# 1-Schematic_ACSE.net
KiCad netlist of a schematic drawn in EasyEDA
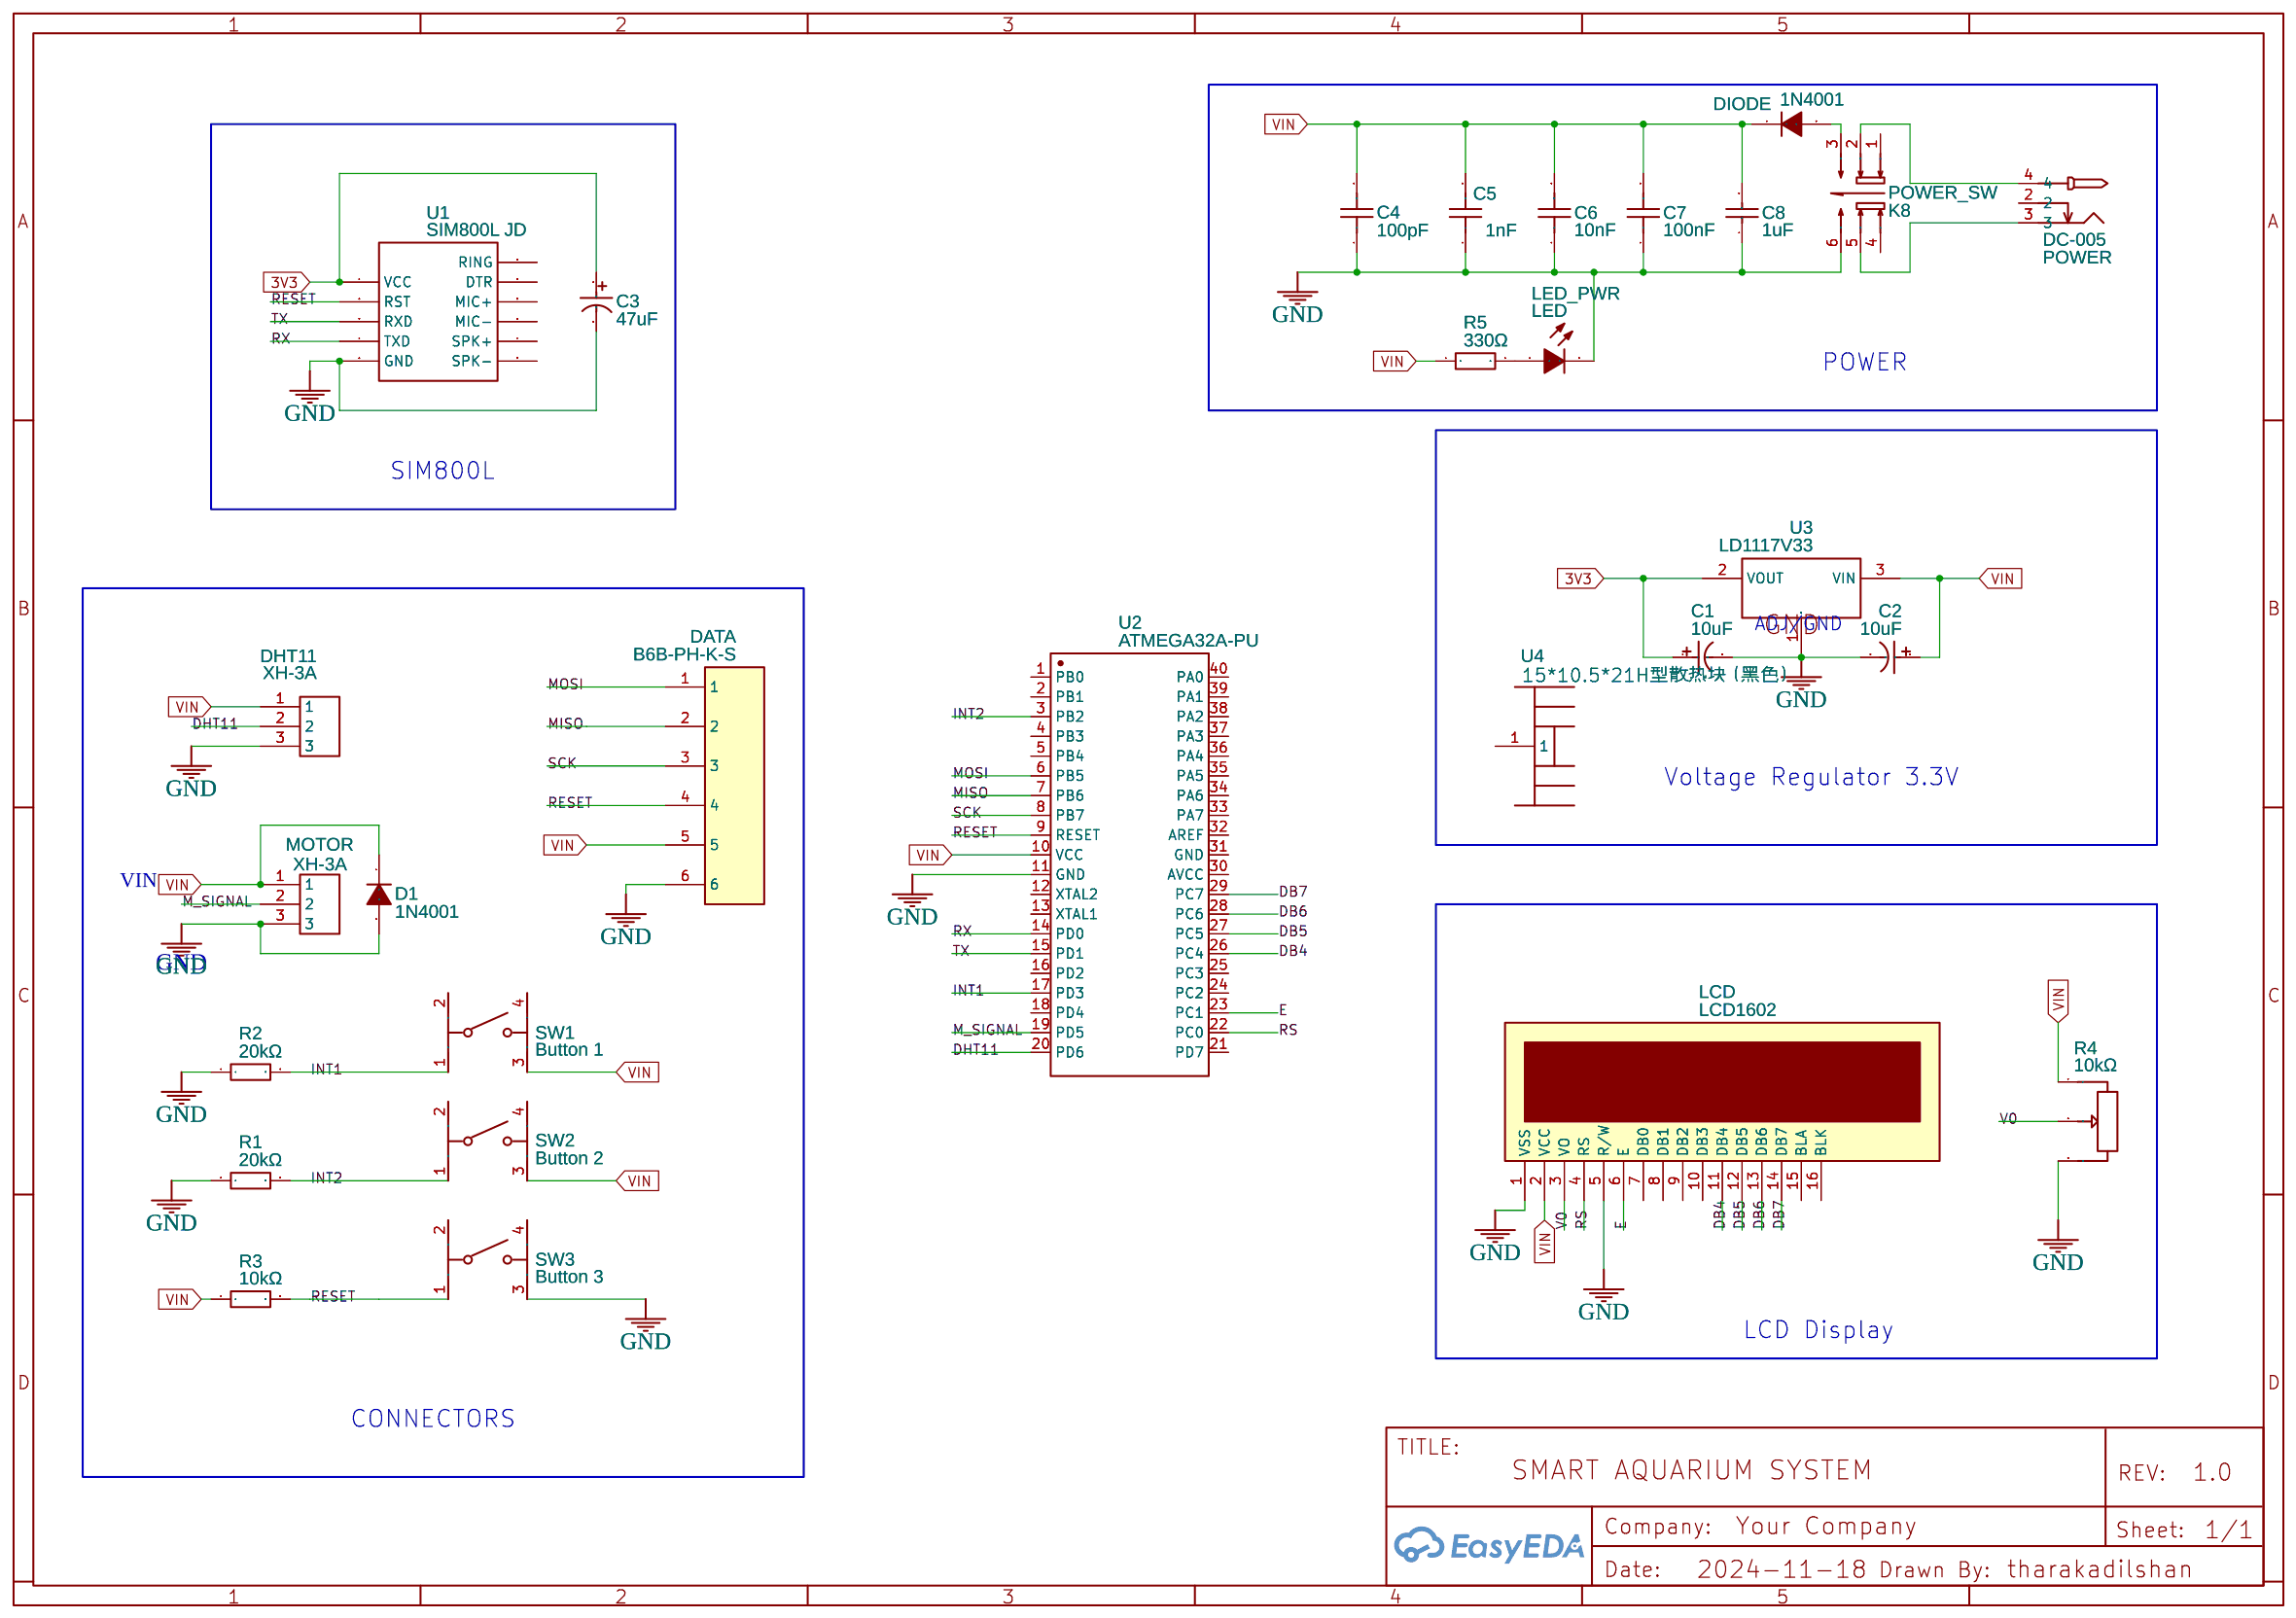
[diagram p0: schematic sheet]

(export (version "E")
  (design (tool "Eeschema 10.0.6"))
  (components
    (comp (ref "C1")
      (value "10uF")
      (fields
        (field (name "Manufacturer Part") "KM106M100E11RR0VH2FP0")
        (field (name "Manufacturer") "CX(承兴)")
      )
      (libsource (lib "") (part "10uf/100V"))
    )
    (comp (ref "C2")
      (value "10uF")
      (fields
        (field (name "Manufacturer Part") "KM106M100E11RR0VH2FP0")
        (field (name "Manufacturer") "CX(承兴)")
      )
      (libsource (lib "") (part "10uf/100V_1"))
    )
    (comp (ref "C3")
      (value "47uF")
      (fields
        (field (name "Manufacturer Part") "KS476M016D07RR0VH2FP0")
        (field (name "Manufacturer") "CX(承兴)")
      )
      (libsource (lib "") (part "47UF16V"))
    )
    (comp (ref "C4")
      (value "100pF")
      (fields
        (field (name "Manufacturer Part") "CC1H101KC4PDSL4B30MF")
        (field (name "Manufacturer") "Dersonic(德尔创)")
      )
      (libsource (lib "") (part "CC1H101KC4PDSL4B30MF"))
    )
    (comp (ref "C5")
      (value "1nF")
      (fields
        (field (name "Manufacturer Part") "CC1H102MC1PDB44B30MF")
        (field (name "Manufacturer") "Dersonic(德尔创)")
      )
      (libsource (lib "") (part "CC1H102MC1PDB44B30MF"))
    )
    (comp (ref "C6")
      (value "10nF")
      (fields
        (field (name "Manufacturer Part") "CC1H103ZC4PD3F4D30MF")
        (field (name "Manufacturer") "Dersonic(德尔创)")
      )
      (libsource (lib "") (part "CC1H103ZC4PD3F4D30MF"))
    )
    (comp (ref "C7")
      (value "100nF")
      (fields
        (field (name "Manufacturer Part") "CC1H104ZC1PD3F5P30MF")
        (field (name "Manufacturer") "Dersonic(德尔创)")
      )
      (libsource (lib "") (part "CC1H104ZC1PD3F5P30MF"))
    )
    (comp (ref "C8")
      (value "1uF")
      (fields (field (name "Manufacturer Part") "SR305C105KAR") (field (name "Manufacturer") "Kyocera AVX"))
      (libsource (lib "") (part "SR305C105KAR"))
    )
    (comp (ref "D1")
      (value "1N4001")
      (fields (field (name "Manufacturer Part") "1N4001-E3/73") (field (name "Manufacturer") "VISHAY(威世)"))
      (libsource (lib "") (part "1N4001-E3/73"))
    )
    (comp (ref "DATA")
      (value "B6B-PH-K-S")
      (fields (field (name "Manufacturer Part") "B6B-PH-K-S(LF)(SN)") (field (name "Manufacturer") "JST"))
      (libsource (lib "") (part "B6B-PH-K-S(LF)(SN)"))
    )
    (comp (ref "DHT11")
      (value "XH-3A")
      (fields (field (name "Manufacturer") "BOOMELE(博穆精密)"))
      (libsource (lib "") (part "XH-3A_1"))
    )
    (comp (ref "DIODE")
      (value "1N4001")
      (fields (field (name "Manufacturer Part") "1N4001-E3/73") (field (name "Manufacturer") "VISHAY(威世)"))
      (libsource (lib "") (part "1N4001-E3/73_1"))
    )
    (comp (ref "LCD")
      (value "LCD1602")
      (fields
        (field (name "Manufacturer Part") "LCM1602K-NSW-BBW")
        (field (name "Manufacturer") "LONTECH(厦门龙特)")
      )
      (libsource (lib "") (part "LCD1602"))
    )
    (comp (ref "LED_PWR")
      (value "LED")
      (fields
        (field (name "Manufacturer Part") "204-10SDRD/S530-A3-L")
        (field (name "Manufacturer") "EVERLIGHT(亿光)")
      )
      (libsource (lib "") (part "204-10SDRD/S530-A3-L"))
    )
    (comp (ref "MOTOR")
      (value "XH-3A")
      (fields (field (name "Manufacturer") "BOOMELE(博穆精密)"))
      (libsource (lib "") (part "XH-3A"))
    )
    (comp (ref "POWER")
      (value "DC-005")
      (fields (field (name "Manufacturer Part") "DC-005 2.0") (field (name "Manufacturer") "BOOMELE(博穆精密)"))
      (libsource (lib "") (part "DC-005 5.5-2.0MM"))
    )
    (comp (ref "POWER_SW")
      (value "K8")
      (fields (field (name "Manufacturer Part") "K8-7071D-L1") (field (name "Manufacturer") "韩国韩荣"))
      (libsource (lib "") (part "K8-7071D-L1"))
    )
    (comp (ref "R1")
      (value "20kΩ")
      (fields
        (field (name "Manufacturer Part") "MFR0W4F2002A50")
        (field (name "Manufacturer") "UNI-ROYAL(厚声)")
      )
      (libsource (lib "") (part "MFR0W4F2002A50"))
    )
    (comp (ref "R2")
      (value "20kΩ")
      (fields
        (field (name "Manufacturer Part") "MFR0W4F2002A50")
        (field (name "Manufacturer") "UNI-ROYAL(厚声)")
      )
      (libsource (lib "") (part "MFR0W4F2002A50"))
    )
    (comp (ref "R3")
      (value "10kΩ")
      (fields
        (field (name "Manufacturer Part") "CFR0W4J0103A50")
        (field (name "Manufacturer") "UNI-ROYAL(厚声)")
      )
      (libsource (lib "") (part "CFR0W4J0103A50"))
    )
    (comp (ref "R4")
      (value "10kΩ")
      (fields
        (field (name "Manufacturer Part") "CT-6ETV 10K OHM (103)")
        (field (name "Manufacturer") "NIDEC(尼得科)")
      )
      (libsource (lib "") (part "CT-6ETV 10K OHM (103)"))
    )
    (comp (ref "R5")
      (value "330Ω")
      (fields
        (field (name "Manufacturer Part") "CFR0W4J0331A50")
        (field (name "Manufacturer") "UNI-ROYAL(厚声)")
      )
      (libsource (lib "") (part "CFR0W4J0331A50"))
    )
    (comp (ref "SW1")
      (value "Button 1")
      (fields (field (name "Manufacturer Part") "C268224") (field (name "Manufacturer") "BBJ"))
      (libsource (lib "") (part "Button-6x6x6mm"))
    )
    (comp (ref "SW2")
      (value "Button 2")
      (fields
        (field (name "Manufacturer Part") "Switch,6*6*6Plastic head,260G, 0.25mm,Straight line")
        (field (name "Manufacturer") "BBJ")
      )
      (libsource (lib "") (part "Button-6x6x6mm"))
    )
    (comp (ref "SW3")
      (value "Button 3")
      (fields
        (field (name "Manufacturer Part") "Switch,6*6*6Plastic head,260G, 0.25mm,Straight line")
        (field (name "Manufacturer") "BBJ")
      )
      (libsource (lib "") (part "Button-6x6x6mm"))
    )
    (comp (ref "U1") (value "SIM800L JD") (libsource (lib "") (part "SIM800L JD")))
    (comp (ref "U2")
      (value "ATMEGA32A-PU")
      (fields (field (name "Manufacturer") "MICROCHIP(美国微芯)"))
      (libsource (lib "") (part "ATMEGA32A-PU"))
    )
    (comp (ref "U3")
      (value "LD1117V33")
      (fields (field (name "Manufacturer") "ST(意法半导体)"))
      (libsource (lib "") (part "LD1117V33"))
    )
    (comp (ref "U4")
      (value "15*10.5*21H型散热块（黑色）")
      (fields (field (name "Manufacturer Part") "15*10.5*21") (field (name "Manufacturer") "XSD(鑫顺达)"))
      (libsource (lib "") (part "15*10.5*21H型散热块（黑色）"))
    )
  )
  (nets
    (net (code "1") (name "/DB4") (class "Default")
      (node (ref "LCD") (pin "11") (pinfunction "DB4_11") (pintype "unspecified"))
      (node (ref "U2") (pin "26") (pinfunction "PC4_26") (pintype "unspecified"))
    )
    (net (code "2") (name "/DB5") (class "Default")
      (node (ref "LCD") (pin "12") (pinfunction "DB5_12") (pintype "unspecified"))
      (node (ref "U2") (pin "27") (pinfunction "PC5_27") (pintype "unspecified"))
    )
    (net (code "3") (name "/DB6") (class "Default")
      (node (ref "LCD") (pin "13") (pinfunction "DB6_13") (pintype "unspecified"))
      (node (ref "U2") (pin "28") (pinfunction "PC6_28") (pintype "unspecified"))
    )
    (net (code "4") (name "/DB7") (class "Default")
      (node (ref "LCD") (pin "14") (pinfunction "DB7_14") (pintype "unspecified"))
      (node (ref "U2") (pin "29") (pinfunction "PC7_29") (pintype "unspecified"))
    )
    (net (code "5") (name "/DHT11") (class "Default")
      (node (ref "DHT11") (pin "2") (pinfunction "2_2") (pintype "unspecified"))
      (node (ref "U2") (pin "20") (pinfunction "PD6_20") (pintype "unspecified"))
    )
    (net (code "6") (name "/E") (class "Default")
      (node (ref "LCD") (pin "6") (pinfunction "E_6") (pintype "unspecified"))
      (node (ref "U2") (pin "23") (pinfunction "PC1_23") (pintype "unspecified"))
    )
    (net (code "7") (name "/INT1") (class "Default")
      (node (ref "R2") (pin "2") (pinfunction "2_2") (pintype "input"))
      (node (ref "SW1") (pin "1") (pinfunction "1_1") (pintype "unspecified"))
      (node (ref "U2") (pin "17") (pinfunction "PD3_17") (pintype "unspecified"))
    )
    (net (code "8") (name "/INT2") (class "Default")
      (node (ref "R1") (pin "2") (pinfunction "2_2") (pintype "input"))
      (node (ref "SW2") (pin "1") (pinfunction "1_1") (pintype "unspecified"))
      (node (ref "U2") (pin "3") (pinfunction "PB2_3") (pintype "unspecified"))
    )
    (net (code "9") (name "/MISO") (class "Default")
      (node (ref "DATA") (pin "2") (pinfunction "2_2") (pintype "input"))
      (node (ref "U2") (pin "7") (pinfunction "PB6_7") (pintype "unspecified"))
    )
    (net (code "10") (name "/MOSI") (class "Default")
      (node (ref "DATA") (pin "1") (pinfunction "1_1") (pintype "input"))
      (node (ref "U2") (pin "6") (pinfunction "PB5_6") (pintype "unspecified"))
    )
    (net (code "11") (name "/M_SIGNAL") (class "Default")
      (node (ref "MOTOR") (pin "2") (pinfunction "2_2") (pintype "unspecified"))
      (node (ref "U2") (pin "19") (pinfunction "PD5_19") (pintype "unspecified"))
    )
    (net (code "12") (name "/RESET") (class "Default")
      (node (ref "DATA") (pin "4") (pinfunction "4_4") (pintype "input"))
      (node (ref "R3") (pin "2") (pinfunction "2_2") (pintype "input"))
      (node (ref "SW3") (pin "1") (pinfunction "1_1") (pintype "unspecified"))
      (node (ref "U1") (pin "2") (pinfunction "RST_2") (pintype "unspecified"))
      (node (ref "U2") (pin "9") (pinfunction "RESET_9") (pintype "unspecified"))
    )
    (net (code "13") (name "/RS") (class "Default")
      (node (ref "LCD") (pin "4") (pinfunction "RS_4") (pintype "unspecified"))
      (node (ref "U2") (pin "22") (pinfunction "PC0_22") (pintype "unspecified"))
    )
    (net (code "14") (name "/RX") (class "Default")
      (node (ref "U1") (pin "4") (pinfunction "TXD_4") (pintype "unspecified"))
      (node (ref "U2") (pin "14") (pinfunction "PD0_14") (pintype "unspecified"))
    )
    (net (code "15") (name "/SCK") (class "Default")
      (node (ref "DATA") (pin "3") (pinfunction "3_3") (pintype "input"))
      (node (ref "U2") (pin "8") (pinfunction "PB7_8") (pintype "unspecified"))
    )
    (net (code "16") (name "/TX") (class "Default")
      (node (ref "U1") (pin "3") (pinfunction "RXD_3") (pintype "unspecified"))
      (node (ref "U2") (pin "15") (pinfunction "PD1_15") (pintype "unspecified"))
    )
    (net (code "17") (name "/V0") (class "Default")
      (node (ref "LCD") (pin "3") (pinfunction "VO_3") (pintype "unspecified"))
      (node (ref "R4") (pin "2") (pinfunction "2_2") (pintype "unspecified"))
    )
    (net (code "18") (name "3V3") (class "Default")
      (node (ref "C1") (pin "1") (pinfunction "1_1") (pintype "input"))
      (node (ref "C3") (pin "1") (pinfunction "1_1") (pintype "input"))
      (node (ref "U1") (pin "1") (pinfunction "VCC_1") (pintype "unspecified"))
      (node (ref "U3") (pin "2") (pinfunction "VOUT_2") (pintype "passive"))
    )
    (net (code "19") (name "GND") (class "Default")
      (node (ref "C1") (pin "2") (pinfunction "2_2") (pintype "input"))
      (node (ref "C2") (pin "2") (pinfunction "2_2") (pintype "input"))
      (node (ref "C3") (pin "2") (pinfunction "2_2") (pintype "input"))
      (node (ref "C4") (pin "1") (pinfunction "1_1") (pintype "unspecified"))
      (node (ref "C5") (pin "1") (pinfunction "1_1") (pintype "unspecified"))
      (node (ref "C6") (pin "1") (pinfunction "1_1") (pintype "unspecified"))
      (node (ref "C7") (pin "1") (pinfunction "1_1") (pintype "unspecified"))
      (node (ref "C8") (pin "1") (pinfunction "1_1") (pintype "input"))
      (node (ref "D1") (pin "2") (pinfunction "A_2") (pintype "unspecified"))
      (node (ref "DATA") (pin "6") (pinfunction "6_6") (pintype "input"))
      (node (ref "DHT11") (pin "3") (pinfunction "3_3") (pintype "unspecified"))
      (node (ref "LCD") (pin "1") (pinfunction "VSS_1") (pintype "unspecified"))
      (node (ref "LCD") (pin "5") (pinfunction "R/W_5") (pintype "unspecified"))
      (node (ref "LED_PWR") (pin "2") (pinfunction "C_2") (pintype "input"))
      (node (ref "MOTOR") (pin "3") (pinfunction "3_3") (pintype "unspecified"))
      (node (ref "POWER_SW") (pin "6") (pinfunction "6_6") (pintype "unspecified"))
      (node (ref "R1") (pin "1") (pinfunction "1_1") (pintype "input"))
      (node (ref "R2") (pin "1") (pinfunction "1_1") (pintype "input"))
      (node (ref "R4") (pin "3") (pinfunction "3_3") (pintype "unspecified"))
      (node (ref "SW3") (pin "3") (pinfunction "3_3") (pintype "unspecified"))
      (node (ref "U1") (pin "5") (pinfunction "GND_5") (pintype "unspecified"))
      (node (ref "U2") (pin "11") (pinfunction "GND_11") (pintype "unspecified"))
      (node (ref "U3") (pin "1") (pinfunction "GND_1") (pintype "unspecified"))
    )
    (net (code "20") (name "Net-(DIODE-A)") (class "Default")
      (node (ref "DIODE") (pin "2") (pinfunction "A_2") (pintype "unspecified"))
      (node (ref "POWER_SW") (pin "3") (pinfunction "3_3") (pintype "unspecified"))
    )
    (net (code "21") (name "Net-(LED_PWR-A)") (class "Default")
      (node (ref "LED_PWR") (pin "1") (pinfunction "A_1") (pintype "input"))
      (node (ref "R5") (pin "2") (pinfunction "2_2") (pintype "input"))
    )
    (net (code "22") (name "Net-(POWER-Pad3)") (class "Default")
      (node (ref "POWER") (pin "3") (pinfunction "3_3") (pintype "unspecified"))
      (node (ref "POWER_SW") (pin "5") (pinfunction "5_5") (pintype "unspecified"))
    )
    (net (code "23") (name "Net-(POWER-Pad4)") (class "Default")
      (node (ref "POWER") (pin "4") (pinfunction "4_4") (pintype "unspecified"))
      (node (ref "POWER_SW") (pin "2") (pinfunction "2_2") (pintype "unspecified"))
    )
    (net (code "24") (name "VIN") (class "Default")
      (node (ref "C2") (pin "1") (pinfunction "1_1") (pintype "input"))
      (node (ref "C4") (pin "2") (pinfunction "2_2") (pintype "unspecified"))
      (node (ref "C5") (pin "2") (pinfunction "2_2") (pintype "unspecified"))
      (node (ref "C6") (pin "2") (pinfunction "2_2") (pintype "unspecified"))
      (node (ref "C7") (pin "2") (pinfunction "2_2") (pintype "unspecified"))
      (node (ref "C8") (pin "2") (pinfunction "2_2") (pintype "input"))
      (node (ref "D1") (pin "1") (pinfunction "K_1") (pintype "unspecified"))
      (node (ref "DATA") (pin "5") (pinfunction "5_5") (pintype "input"))
      (node (ref "DHT11") (pin "1") (pinfunction "1_1") (pintype "unspecified"))
      (node (ref "DIODE") (pin "1") (pinfunction "K_1") (pintype "unspecified"))
      (node (ref "LCD") (pin "2") (pinfunction "VCC_2") (pintype "unspecified"))
      (node (ref "MOTOR") (pin "1") (pinfunction "1_1") (pintype "unspecified"))
      (node (ref "R3") (pin "1") (pinfunction "1_1") (pintype "input"))
      (node (ref "R4") (pin "1") (pinfunction "1_1") (pintype "unspecified"))
      (node (ref "R5") (pin "1") (pinfunction "1_1") (pintype "input"))
      (node (ref "SW1") (pin "3") (pinfunction "3_3") (pintype "unspecified"))
      (node (ref "SW2") (pin "3") (pinfunction "3_3") (pintype "unspecified"))
      (node (ref "U2") (pin "10") (pinfunction "VCC_10") (pintype "unspecified"))
      (node (ref "U3") (pin "3") (pinfunction "VIN_3") (pintype "passive"))
    )
    (net (code "25") (name "unconnected-(LCD-BLA-Pad15)") (class "Default")
      (node (ref "LCD") (pin "15") (pinfunction "BLA_15") (pintype "unspecified"))
    )
    (net (code "26") (name "unconnected-(LCD-BLK-Pad16)") (class "Default")
      (node (ref "LCD") (pin "16") (pinfunction "BLK_16") (pintype "unspecified"))
    )
    (net (code "27") (name "unconnected-(LCD-DB0-Pad7)") (class "Default")
      (node (ref "LCD") (pin "7") (pinfunction "DB0_7") (pintype "unspecified"))
    )
    (net (code "28") (name "unconnected-(LCD-DB1-Pad8)") (class "Default")
      (node (ref "LCD") (pin "8") (pinfunction "DB1_8") (pintype "unspecified"))
    )
    (net (code "29") (name "unconnected-(LCD-DB2-Pad9)") (class "Default")
      (node (ref "LCD") (pin "9") (pinfunction "DB2_9") (pintype "unspecified"))
    )
    (net (code "30") (name "unconnected-(LCD-DB3-Pad10)") (class "Default")
      (node (ref "LCD") (pin "10") (pinfunction "DB3_10") (pintype "unspecified"))
    )
    (net (code "31") (name "unconnected-(POWER-Pad2)") (class "Default")
      (node (ref "POWER") (pin "2") (pinfunction "2_2") (pintype "unspecified"))
    )
    (net (code "32") (name "unconnected-(POWER_SW-Pad1)") (class "Default")
      (node (ref "POWER_SW") (pin "1") (pinfunction "1_1") (pintype "unspecified"))
    )
    (net (code "33") (name "unconnected-(POWER_SW-Pad4)") (class "Default")
      (node (ref "POWER_SW") (pin "4") (pinfunction "4_4") (pintype "unspecified"))
    )
    (net (code "34") (name "unconnected-(SW1-Pad2)") (class "Default")
      (node (ref "SW1") (pin "2") (pinfunction "2_2") (pintype "unspecified"))
    )
    (net (code "35") (name "unconnected-(SW1-Pad4)") (class "Default")
      (node (ref "SW1") (pin "4") (pinfunction "4_4") (pintype "unspecified"))
    )
    (net (code "36") (name "unconnected-(SW2-Pad2)") (class "Default")
      (node (ref "SW2") (pin "2") (pinfunction "2_2") (pintype "unspecified"))
    )
    (net (code "37") (name "unconnected-(SW2-Pad4)") (class "Default")
      (node (ref "SW2") (pin "4") (pinfunction "4_4") (pintype "unspecified"))
    )
    (net (code "38") (name "unconnected-(SW3-Pad2)") (class "Default")
      (node (ref "SW3") (pin "2") (pinfunction "2_2") (pintype "unspecified"))
    )
    (net (code "39") (name "unconnected-(SW3-Pad4)") (class "Default")
      (node (ref "SW3") (pin "4") (pinfunction "4_4") (pintype "unspecified"))
    )
    (net (code "40") (name "unconnected-(U1-DTR-Pad10)") (class "Default")
      (node (ref "U1") (pin "10") (pinfunction "DTR_10") (pintype "unspecified"))
    )
    (net (code "41") (name "unconnected-(U1-MIC+-Pad9)") (class "Default")
      (node (ref "U1") (pin "9") (pinfunction "MIC+_9") (pintype "unspecified"))
    )
    (net (code "42") (name "unconnected-(U1-MIC--Pad8)") (class "Default")
      (node (ref "U1") (pin "8") (pinfunction "MIC-_8") (pintype "unspecified"))
    )
    (net (code "43") (name "unconnected-(U1-RING-Pad11)") (class "Default")
      (node (ref "U1") (pin "11") (pinfunction "RING_11") (pintype "unspecified"))
    )
    (net (code "44") (name "unconnected-(U1-SPK+-Pad7)") (class "Default")
      (node (ref "U1") (pin "7") (pinfunction "SPK+_7") (pintype "unspecified"))
    )
    (net (code "45") (name "unconnected-(U1-SPK--Pad6)") (class "Default")
      (node (ref "U1") (pin "6") (pinfunction "SPK-_6") (pintype "unspecified"))
    )
    (net (code "46") (name "unconnected-(U2-AREF-Pad32)") (class "Default")
      (node (ref "U2") (pin "32") (pinfunction "AREF_32") (pintype "unspecified"))
    )
    (net (code "47") (name "unconnected-(U2-AVCC-Pad30)") (class "Default")
      (node (ref "U2") (pin "30") (pinfunction "AVCC_30") (pintype "unspecified"))
    )
    (net (code "48") (name "unconnected-(U2-GND-Pad31)") (class "Default")
      (node (ref "U2") (pin "31") (pinfunction "GND_31") (pintype "unspecified"))
    )
    (net (code "49") (name "unconnected-(U2-PA0-Pad40)") (class "Default")
      (node (ref "U2") (pin "40") (pinfunction "PA0_40") (pintype "unspecified"))
    )
    (net (code "50") (name "unconnected-(U2-PA1-Pad39)") (class "Default")
      (node (ref "U2") (pin "39") (pinfunction "PA1_39") (pintype "unspecified"))
    )
    (net (code "51") (name "unconnected-(U2-PA2-Pad38)") (class "Default")
      (node (ref "U2") (pin "38") (pinfunction "PA2_38") (pintype "unspecified"))
    )
    (net (code "52") (name "unconnected-(U2-PA3-Pad37)") (class "Default")
      (node (ref "U2") (pin "37") (pinfunction "PA3_37") (pintype "unspecified"))
    )
    (net (code "53") (name "unconnected-(U2-PA4-Pad36)") (class "Default")
      (node (ref "U2") (pin "36") (pinfunction "PA4_36") (pintype "unspecified"))
    )
    (net (code "54") (name "unconnected-(U2-PA5-Pad35)") (class "Default")
      (node (ref "U2") (pin "35") (pinfunction "PA5_35") (pintype "unspecified"))
    )
    (net (code "55") (name "unconnected-(U2-PA6-Pad34)") (class "Default")
      (node (ref "U2") (pin "34") (pinfunction "PA6_34") (pintype "unspecified"))
    )
    (net (code "56") (name "unconnected-(U2-PA7-Pad33)") (class "Default")
      (node (ref "U2") (pin "33") (pinfunction "PA7_33") (pintype "unspecified"))
    )
    (net (code "57") (name "unconnected-(U2-PB0-Pad1)") (class "Default")
      (node (ref "U2") (pin "1") (pinfunction "PB0_1") (pintype "unspecified"))
    )
    (net (code "58") (name "unconnected-(U2-PB1-Pad2)") (class "Default")
      (node (ref "U2") (pin "2") (pinfunction "PB1_2") (pintype "unspecified"))
    )
    (net (code "59") (name "unconnected-(U2-PB3-Pad4)") (class "Default")
      (node (ref "U2") (pin "4") (pinfunction "PB3_4") (pintype "unspecified"))
    )
    (net (code "60") (name "unconnected-(U2-PB4-Pad5)") (class "Default")
      (node (ref "U2") (pin "5") (pinfunction "PB4_5") (pintype "unspecified"))
    )
    (net (code "61") (name "unconnected-(U2-PC2-Pad24)") (class "Default")
      (node (ref "U2") (pin "24") (pinfunction "PC2_24") (pintype "unspecified"))
    )
    (net (code "62") (name "unconnected-(U2-PC3-Pad25)") (class "Default")
      (node (ref "U2") (pin "25") (pinfunction "PC3_25") (pintype "unspecified"))
    )
    (net (code "63") (name "unconnected-(U2-PD2-Pad16)") (class "Default")
      (node (ref "U2") (pin "16") (pinfunction "PD2_16") (pintype "unspecified"))
    )
    (net (code "64") (name "unconnected-(U2-PD4-Pad18)") (class "Default")
      (node (ref "U2") (pin "18") (pinfunction "PD4_18") (pintype "unspecified"))
    )
    (net (code "65") (name "unconnected-(U2-PD7-Pad21)") (class "Default")
      (node (ref "U2") (pin "21") (pinfunction "PD7_21") (pintype "unspecified"))
    )
    (net (code "66") (name "unconnected-(U2-XTAL1-Pad13)") (class "Default")
      (node (ref "U2") (pin "13") (pinfunction "XTAL1_13") (pintype "unspecified"))
    )
    (net (code "67") (name "unconnected-(U2-XTAL2-Pad12)") (class "Default")
      (node (ref "U2") (pin "12") (pinfunction "XTAL2_12") (pintype "unspecified"))
    )
    (net (code "68") (name "unconnected-(U4-Pad1)") (class "Default")
      (node (ref "U4") (pin "1") (pinfunction "1_1") (pintype "unspecified"))
    )
  )
)
